# lan_board.net
KiCad netlist of a schematic drawn in Altium Designer
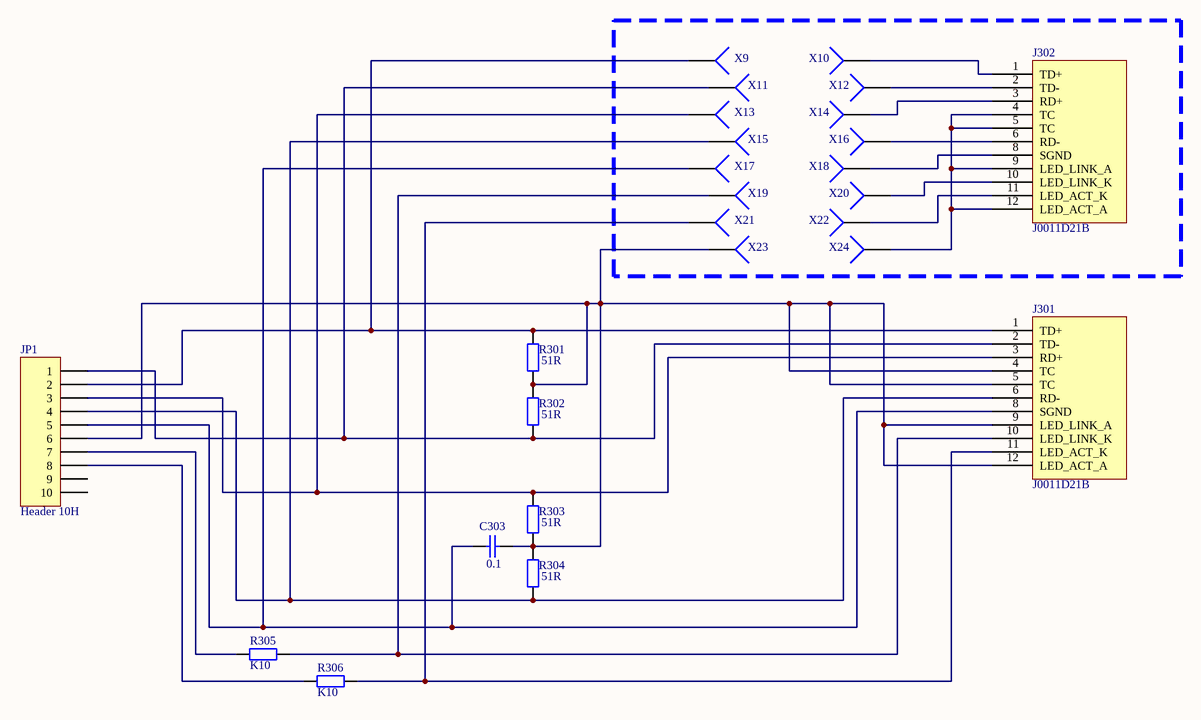
[diagram p0: lan_board.SchDoc]

(export (version "E")
  (design (tool "Eeschema 10.0.6"))
  (components
    (comp (ref "C303")
      (value "0.1")
      (footprint "_0603")
      (description "Capacitor (Semiconductor SIM Model)")
      (fields (field (name "MANUFACTURER") "Generic Components") (field (name "PUBLISHER") "Altium Limited"))
      (libsource (lib "Miscellaneous Devices") (part "Cap Semi"))
    )
    (comp (ref "J301") (value "J0011D21B") (footprint "J0011D21B") (libsource (lib "PAL") (part "J0011D21B")))
    (comp (ref "J302") (value "J0011D21B") (footprint "J0011D21B") (libsource (lib "PAL") (part "J0011D21B")))
    (comp (ref "JP1")
      (value "Header 10H")
      (footprint "HDR2X5")
      (description "Header, 10-Pin, Right Angle")
      (fields (field (name "MANUFACTURER") "Generic Components") (field (name "PUBLISHER") "Altium Limited"))
      (libsource (lib "Miscellaneous Connectors") (part "Header 10H"))
    )
    (comp (ref "R301")
      (value "51R")
      (footprint "_0603")
      (description "Resistor")
      (fields (field (name "MANUFACTURER") "Generic Components") (field (name "PUBLISHER") "Altium Limited"))
      (libsource (lib "") (part "Res2_1"))
    )
    (comp (ref "R302")
      (value "51R")
      (footprint "_0603")
      (description "Resistor")
      (fields (field (name "MANUFACTURER") "Generic Components") (field (name "PUBLISHER") "Altium Limited"))
      (libsource (lib "") (part "Res2_1"))
    )
    (comp (ref "R303")
      (value "51R")
      (footprint "_0603")
      (description "Resistor")
      (fields (field (name "MANUFACTURER") "Generic Components") (field (name "PUBLISHER") "Altium Limited"))
      (libsource (lib "") (part "Res2_1"))
    )
    (comp (ref "R304")
      (value "51R")
      (footprint "_0603")
      (description "Resistor")
      (fields (field (name "MANUFACTURER") "Generic Components") (field (name "PUBLISHER") "Altium Limited"))
      (libsource (lib "") (part "Res2_1"))
    )
    (comp (ref "R305")
      (value "K10")
      (footprint "_0603")
      (description "Resistor")
      (fields (field (name "MANUFACTURER") "Generic Components") (field (name "PUBLISHER") "Altium Limited"))
      (libsource (lib "Miscellaneous Devices") (part "Res2"))
    )
    (comp (ref "R306")
      (value "K10")
      (footprint "_0603")
      (description "Resistor")
      (fields (field (name "MANUFACTURER") "Generic Components") (field (name "PUBLISHER") "Altium Limited"))
      (libsource (lib "Miscellaneous Devices") (part "Res2"))
    )
    (comp (ref "X9")
      (value "~")
      (footprint "PIN1")
      (description "Socket")
      (fields (field (name "MANUFACTURER") "Generic Components") (field (name "PUBLISHER") "Altium Limited"))
      (libsource (lib "Miscellaneous Connectors") (part "Socket"))
    )
    (comp (ref "X10")
      (value "~")
      (footprint "PIN1")
      (description "Socket")
      (fields (field (name "MANUFACTURER") "Generic Components") (field (name "PUBLISHER") "Altium Limited"))
      (libsource (lib "Miscellaneous Connectors") (part "Socket"))
    )
    (comp (ref "X11")
      (value "~")
      (footprint "PIN1")
      (description "Socket")
      (fields (field (name "MANUFACTURER") "Generic Components") (field (name "PUBLISHER") "Altium Limited"))
      (libsource (lib "Miscellaneous Connectors") (part "Socket"))
    )
    (comp (ref "X12")
      (value "~")
      (footprint "PIN1")
      (description "Socket")
      (fields (field (name "MANUFACTURER") "Generic Components") (field (name "PUBLISHER") "Altium Limited"))
      (libsource (lib "Miscellaneous Connectors") (part "Socket"))
    )
    (comp (ref "X13")
      (value "~")
      (footprint "PIN1")
      (description "Socket")
      (fields (field (name "MANUFACTURER") "Generic Components") (field (name "PUBLISHER") "Altium Limited"))
      (libsource (lib "Miscellaneous Connectors") (part "Socket"))
    )
    (comp (ref "X14")
      (value "~")
      (footprint "PIN1")
      (description "Socket")
      (fields (field (name "MANUFACTURER") "Generic Components") (field (name "PUBLISHER") "Altium Limited"))
      (libsource (lib "Miscellaneous Connectors") (part "Socket"))
    )
    (comp (ref "X15")
      (value "~")
      (footprint "PIN1")
      (description "Socket")
      (fields (field (name "MANUFACTURER") "Generic Components") (field (name "PUBLISHER") "Altium Limited"))
      (libsource (lib "Miscellaneous Connectors") (part "Socket"))
    )
    (comp (ref "X16")
      (value "~")
      (footprint "PIN1")
      (description "Socket")
      (fields (field (name "MANUFACTURER") "Generic Components") (field (name "PUBLISHER") "Altium Limited"))
      (libsource (lib "Miscellaneous Connectors") (part "Socket"))
    )
    (comp (ref "X17")
      (value "~")
      (footprint "PIN1")
      (description "Socket")
      (fields (field (name "MANUFACTURER") "Generic Components") (field (name "PUBLISHER") "Altium Limited"))
      (libsource (lib "Miscellaneous Connectors") (part "Socket"))
    )
    (comp (ref "X18")
      (value "~")
      (footprint "PIN1")
      (description "Socket")
      (fields (field (name "MANUFACTURER") "Generic Components") (field (name "PUBLISHER") "Altium Limited"))
      (libsource (lib "Miscellaneous Connectors") (part "Socket"))
    )
    (comp (ref "X19")
      (value "~")
      (footprint "PIN1")
      (description "Socket")
      (fields (field (name "MANUFACTURER") "Generic Components") (field (name "PUBLISHER") "Altium Limited"))
      (libsource (lib "Miscellaneous Connectors") (part "Socket"))
    )
    (comp (ref "X20")
      (value "~")
      (footprint "PIN1")
      (description "Socket")
      (fields (field (name "MANUFACTURER") "Generic Components") (field (name "PUBLISHER") "Altium Limited"))
      (libsource (lib "Miscellaneous Connectors") (part "Socket"))
    )
    (comp (ref "X21")
      (value "~")
      (footprint "PIN1")
      (description "Socket")
      (fields (field (name "MANUFACTURER") "Generic Components") (field (name "PUBLISHER") "Altium Limited"))
      (libsource (lib "Miscellaneous Connectors") (part "Socket"))
    )
    (comp (ref "X22")
      (value "~")
      (footprint "PIN1")
      (description "Socket")
      (fields (field (name "MANUFACTURER") "Generic Components") (field (name "PUBLISHER") "Altium Limited"))
      (libsource (lib "Miscellaneous Connectors") (part "Socket"))
    )
    (comp (ref "X23")
      (value "~")
      (footprint "PIN1")
      (description "Socket")
      (fields (field (name "MANUFACTURER") "Generic Components") (field (name "PUBLISHER") "Altium Limited"))
      (libsource (lib "Miscellaneous Connectors") (part "Socket"))
    )
    (comp (ref "X24")
      (value "~")
      (footprint "PIN1")
      (description "Socket")
      (fields (field (name "MANUFACTURER") "Generic Components") (field (name "PUBLISHER") "Altium Limited"))
      (libsource (lib "Miscellaneous Connectors") (part "Socket"))
    )
  )
  (nets
    (net (code "1") (name "Net-(J301-LED_ACT_A)") (class "Default")
      (node (ref "C303") (pin "2") (pinfunction "2_2") (pintype "passive"))
      (node (ref "J301") (pin "12") (pinfunction "LED_ACT_A_12") (pintype "passive"))
      (node (ref "J301") (pin "4") (pinfunction "TC_4") (pintype "passive"))
      (node (ref "J301") (pin "5") (pinfunction "TC_5") (pintype "passive"))
      (node (ref "J301") (pin "9") (pinfunction "LED_LINK_A_9") (pintype "passive"))
      (node (ref "JP1") (pin "6") (pinfunction "6_6") (pintype "passive"))
      (node (ref "R301") (pin "2") (pinfunction "2_2") (pintype "passive"))
      (node (ref "R302") (pin "1") (pinfunction "1_1") (pintype "passive"))
      (node (ref "R303") (pin "2") (pinfunction "2_2") (pintype "passive"))
      (node (ref "R304") (pin "1") (pinfunction "1_1") (pintype "passive"))
      (node (ref "X23") (pin "1") (pinfunction "1_1") (pintype "passive"))
    )
    (net (code "2") (name "Net-(J301-LED_ACT_K)") (class "Default")
      (node (ref "J301") (pin "11") (pinfunction "LED_ACT_K_11") (pintype "passive"))
      (node (ref "R306") (pin "1") (pinfunction "1_1") (pintype "passive"))
      (node (ref "X21") (pin "1") (pinfunction "1_1") (pintype "passive"))
    )
    (net (code "3") (name "Net-(J301-LED_LINK_K)") (class "Default")
      (node (ref "J301") (pin "10") (pinfunction "LED_LINK_K_10") (pintype "passive"))
      (node (ref "R305") (pin "1") (pinfunction "1_1") (pintype "passive"))
      (node (ref "X19") (pin "1") (pinfunction "1_1") (pintype "passive"))
    )
    (net (code "4") (name "Net-(J301-RD+)") (class "Default")
      (node (ref "J301") (pin "3") (pinfunction "RD+_3") (pintype "passive"))
      (node (ref "JP1") (pin "3") (pinfunction "3_3") (pintype "passive"))
      (node (ref "R303") (pin "1") (pinfunction "1_1") (pintype "passive"))
      (node (ref "X13") (pin "1") (pinfunction "1_1") (pintype "passive"))
    )
    (net (code "5") (name "Net-(J301-RD-)") (class "Default")
      (node (ref "J301") (pin "6") (pinfunction "RD-_6") (pintype "passive"))
      (node (ref "JP1") (pin "4") (pinfunction "4_4") (pintype "passive"))
      (node (ref "R304") (pin "2") (pinfunction "2_2") (pintype "passive"))
      (node (ref "X15") (pin "1") (pinfunction "1_1") (pintype "passive"))
    )
    (net (code "6") (name "Net-(J301-SGND)") (class "Default")
      (node (ref "C303") (pin "1") (pinfunction "1_1") (pintype "passive"))
      (node (ref "J301") (pin "8") (pinfunction "SGND_8") (pintype "passive"))
      (node (ref "JP1") (pin "5") (pinfunction "5_5") (pintype "passive"))
      (node (ref "X17") (pin "1") (pinfunction "1_1") (pintype "passive"))
    )
    (net (code "7") (name "Net-(J301-TD+)") (class "Default")
      (node (ref "J301") (pin "1") (pinfunction "TD+_1") (pintype "passive"))
      (node (ref "JP1") (pin "2") (pinfunction "2_2") (pintype "passive"))
      (node (ref "R301") (pin "1") (pinfunction "1_1") (pintype "passive"))
      (node (ref "X9") (pin "1") (pinfunction "1_1") (pintype "passive"))
    )
    (net (code "8") (name "Net-(J301-TD-)") (class "Default")
      (node (ref "J301") (pin "2") (pinfunction "TD-_2") (pintype "passive"))
      (node (ref "JP1") (pin "1") (pinfunction "1_1") (pintype "passive"))
      (node (ref "R302") (pin "2") (pinfunction "2_2") (pintype "passive"))
      (node (ref "X11") (pin "1") (pinfunction "1_1") (pintype "passive"))
    )
    (net (code "9") (name "Net-(J302-LED_ACT_A)") (class "Default")
      (node (ref "J302") (pin "12") (pinfunction "LED_ACT_A_12") (pintype "passive"))
      (node (ref "J302") (pin "4") (pinfunction "TC_4") (pintype "passive"))
      (node (ref "J302") (pin "5") (pinfunction "TC_5") (pintype "passive"))
      (node (ref "J302") (pin "9") (pinfunction "LED_LINK_A_9") (pintype "passive"))
      (node (ref "X24") (pin "1") (pinfunction "1_1") (pintype "passive"))
    )
    (net (code "10") (name "Net-(J302-LED_ACT_K)") (class "Default")
      (node (ref "J302") (pin "11") (pinfunction "LED_ACT_K_11") (pintype "passive"))
      (node (ref "X22") (pin "1") (pinfunction "1_1") (pintype "passive"))
    )
    (net (code "11") (name "Net-(J302-LED_LINK_K)") (class "Default")
      (node (ref "J302") (pin "10") (pinfunction "LED_LINK_K_10") (pintype "passive"))
      (node (ref "X20") (pin "1") (pinfunction "1_1") (pintype "passive"))
    )
    (net (code "12") (name "Net-(J302-RD+)") (class "Default")
      (node (ref "J302") (pin "3") (pinfunction "RD+_3") (pintype "passive"))
      (node (ref "X14") (pin "1") (pinfunction "1_1") (pintype "passive"))
    )
    (net (code "13") (name "Net-(J302-RD-)") (class "Default")
      (node (ref "J302") (pin "6") (pinfunction "RD-_6") (pintype "passive"))
      (node (ref "X16") (pin "1") (pinfunction "1_1") (pintype "passive"))
    )
    (net (code "14") (name "Net-(J302-SGND)") (class "Default")
      (node (ref "J302") (pin "8") (pinfunction "SGND_8") (pintype "passive"))
      (node (ref "X18") (pin "1") (pinfunction "1_1") (pintype "passive"))
    )
    (net (code "15") (name "Net-(J302-TD+)") (class "Default")
      (node (ref "J302") (pin "1") (pinfunction "TD+_1") (pintype "passive"))
      (node (ref "X10") (pin "1") (pinfunction "1_1") (pintype "passive"))
    )
    (net (code "16") (name "Net-(J302-TD-)") (class "Default")
      (node (ref "J302") (pin "2") (pinfunction "TD-_2") (pintype "passive"))
      (node (ref "X12") (pin "1") (pinfunction "1_1") (pintype "passive"))
    )
    (net (code "17") (name "Net-(JP1-Pad7)") (class "Default")
      (node (ref "JP1") (pin "7") (pinfunction "7_7") (pintype "passive"))
      (node (ref "R305") (pin "2") (pinfunction "2_2") (pintype "passive"))
    )
    (net (code "18") (name "Net-(JP1-Pad8)") (class "Default")
      (node (ref "JP1") (pin "8") (pinfunction "8_8") (pintype "passive"))
      (node (ref "R306") (pin "2") (pinfunction "2_2") (pintype "passive"))
    )
    (net (code "19") (name "unconnected-(JP1-Pad9)") (class "Default")
      (node (ref "JP1") (pin "9") (pinfunction "9_9") (pintype "passive"))
    )
    (net (code "20") (name "unconnected-(JP1-Pad10)") (class "Default")
      (node (ref "JP1") (pin "10") (pinfunction "10_10") (pintype "passive"))
    )
  )
)
